# XBee1.net
KiCad netlist of a schematic drawn in EAGLE
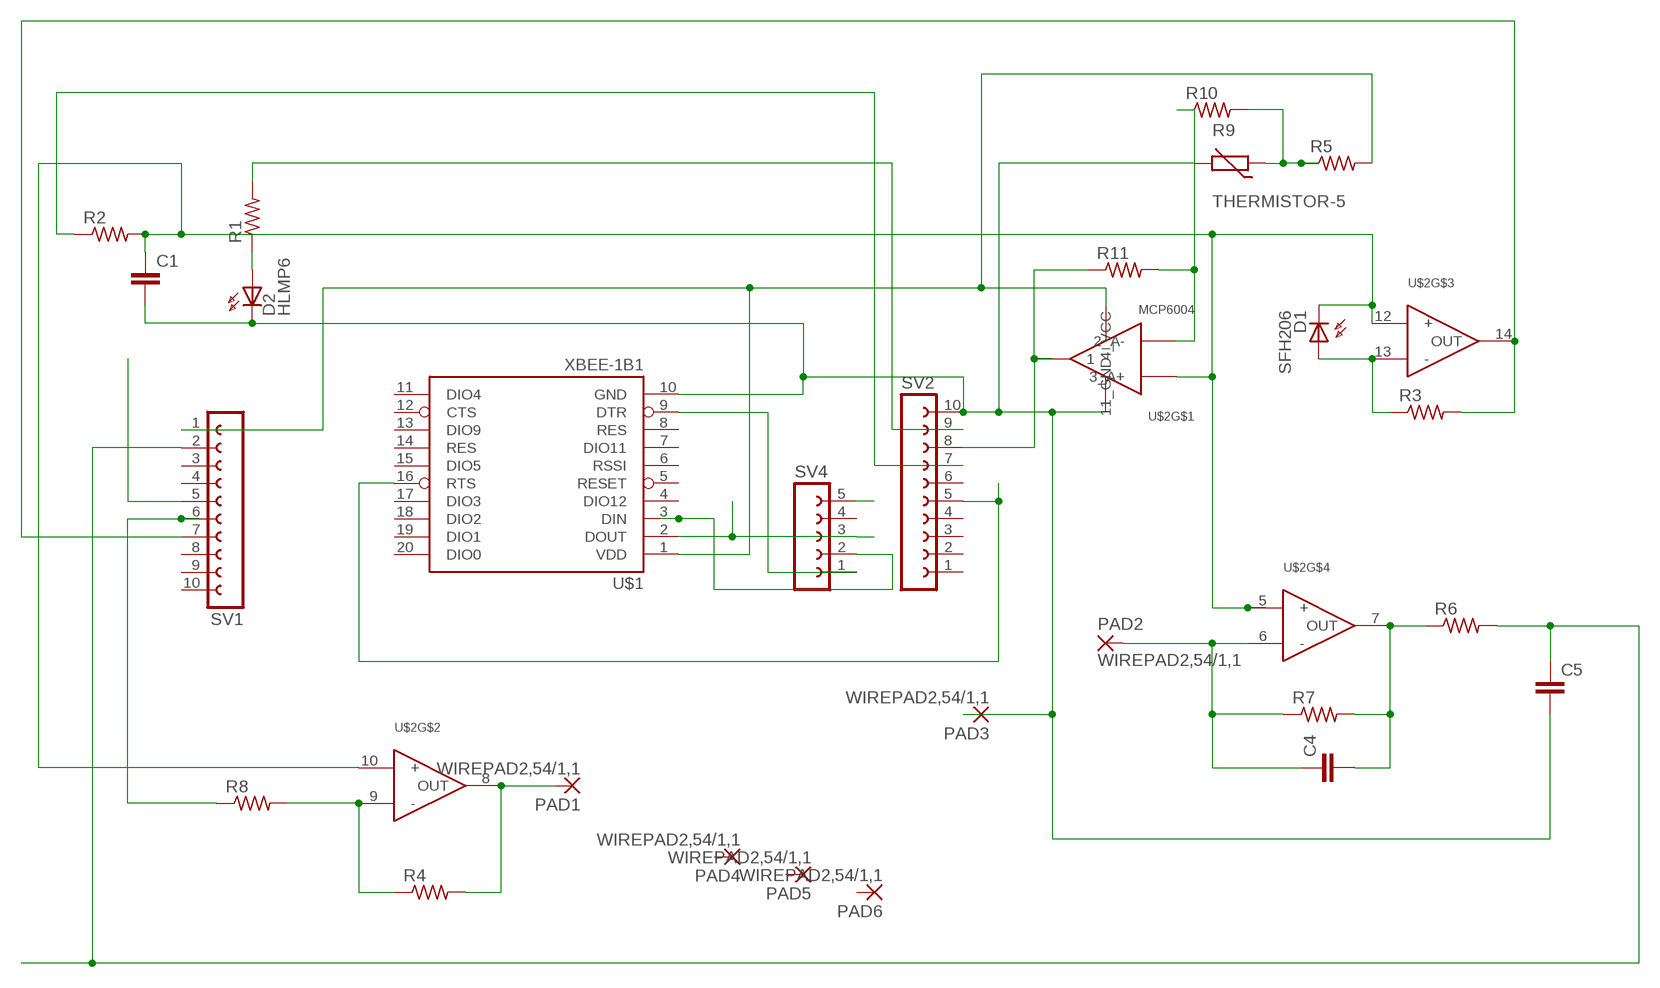
[diagram p0: schematic, sheet 1]

(export (version "E")
  (design (tool "Eeschema 10.0.6"))
  (components
    (comp (ref "C1")
      (value "C-EUC1206")
      (footprint "eagle-import:C1206")
      (libsource (lib "eagle-import") (part "C-EUC1206"))
    )
    (comp (ref "C4")
      (value "C-EUC1206")
      (footprint "eagle-import:C1206")
      (libsource (lib "eagle-import") (part "C-EUC1206"))
    )
    (comp (ref "C5")
      (value "C-EUC1206")
      (footprint "eagle-import:C1206")
      (libsource (lib "eagle-import") (part "C-EUC1206"))
    )
    (comp (ref "D1")
      (value "SFH206")
      (footprint "eagle-import:SFH206")
      (fields (field (name "MPN") "SFH206K"))
      (libsource (lib "eagle-import") (part "SFH206"))
    )
    (comp (ref "D2")
      (value "HLMP6")
      (footprint "eagle-import:HLMP6")
      (fields (field (name "MF") "AGILENT TECHNOLOGIES") (field (name "MPN") "HLMP-6500"))
      (libsource (lib "eagle-import") (part "HLMP6"))
    )
    (comp (ref "PAD1")
      (value "WIREPAD2,54/1,1")
      (footprint "eagle-import:2,54_1,1")
      (libsource (lib "eagle-import") (part "WIREPAD2,54/1,1"))
    )
    (comp (ref "PAD2")
      (value "WIREPAD2,54/1,1")
      (footprint "eagle-import:2,54_1,1")
      (libsource (lib "eagle-import") (part "WIREPAD2,54/1,1"))
    )
    (comp (ref "PAD3")
      (value "WIREPAD2,54/1,1")
      (footprint "eagle-import:2,54_1,1")
      (libsource (lib "eagle-import") (part "WIREPAD2,54/1,1"))
    )
    (comp (ref "PAD4")
      (value "WIREPAD2,54/1,1")
      (footprint "eagle-import:2,54_1,1")
      (libsource (lib "eagle-import") (part "WIREPAD2,54/1,1"))
    )
    (comp (ref "PAD5")
      (value "WIREPAD2,54/1,1")
      (footprint "eagle-import:2,54_1,1")
      (libsource (lib "eagle-import") (part "WIREPAD2,54/1,1"))
    )
    (comp (ref "PAD6")
      (value "WIREPAD2,54/1,1")
      (footprint "eagle-import:2,54_1,1")
      (libsource (lib "eagle-import") (part "WIREPAD2,54/1,1"))
    )
    (comp (ref "R1")
      (value "R-US_M1206")
      (footprint "eagle-import:M1206")
      (libsource (lib "eagle-import") (part "R-US_M1206"))
    )
    (comp (ref "R2")
      (value "R-US_M1206")
      (footprint "eagle-import:M1206")
      (libsource (lib "eagle-import") (part "R-US_M1206"))
    )
    (comp (ref "R3")
      (value "R-US_M1206")
      (footprint "eagle-import:M1206")
      (libsource (lib "eagle-import") (part "R-US_M1206"))
    )
    (comp (ref "R4")
      (value "R-US_M1206")
      (footprint "eagle-import:M1206")
      (libsource (lib "eagle-import") (part "R-US_M1206"))
    )
    (comp (ref "R5")
      (value "R-US_M1206")
      (footprint "eagle-import:M1206")
      (libsource (lib "eagle-import") (part "R-US_M1206"))
    )
    (comp (ref "R6")
      (value "R-US_M1206")
      (footprint "eagle-import:M1206")
      (libsource (lib "eagle-import") (part "R-US_M1206"))
    )
    (comp (ref "R7")
      (value "R-US_M1206")
      (footprint "eagle-import:M1206")
      (libsource (lib "eagle-import") (part "R-US_M1206"))
    )
    (comp (ref "R8")
      (value "R-US_M1206")
      (footprint "eagle-import:M1206")
      (libsource (lib "eagle-import") (part "R-US_M1206"))
    )
    (comp (ref "R9")
      (value "THERMISTOR-5")
      (footprint "eagle-import:R-5")
      (libsource (lib "eagle-import") (part "THERMISTOR-5"))
    )
    (comp (ref "R10")
      (value "R-US_M1206")
      (footprint "eagle-import:M1206")
      (libsource (lib "eagle-import") (part "R-US_M1206"))
    )
    (comp (ref "R11")
      (value "R-US_M1206")
      (footprint "eagle-import:M1206")
      (libsource (lib "eagle-import") (part "R-US_M1206"))
    )
    (comp (ref "SV1")
      (value "FE10-1")
      (footprint "eagle-import:FE10")
      (libsource (lib "eagle-import") (part "FE10-1"))
    )
    (comp (ref "SV2")
      (value "FE10-1")
      (footprint "eagle-import:FE10")
      (libsource (lib "eagle-import") (part "FE10-1"))
    )
    (comp (ref "SV4")
      (value "FE05-1")
      (footprint "eagle-import:FE05-1")
      (libsource (lib "eagle-import") (part "FE05-1"))
    )
    (comp (ref "U$1")
      (value "XBEE-1B1")
      (footprint "eagle-import:XBEE-1")
      (libsource (lib "eagle-import") (part "XBEE-1B1"))
    )
    (comp (ref "U$2")
      (value "MCP6004")
      (footprint "eagle-import:SO014")
      (libsource (lib "eagle-import") (part "MCP6004"))
    )
  )
  (nets
    (net (code "1") (name "Net-(C5-Pad1)") (class "Default")
      (node (ref "C5") (pin "1") (pinfunction "1_1") (pintype "passive"))
      (node (ref "R6") (pin "2") (pinfunction "2_2") (pintype "passive"))
      (node (ref "SV1") (pin "2") (pinfunction "2_2") (pintype "passive"))
    )
    (net (code "2") (name "Net-(D1-C)") (class "Default")
      (node (ref "C1") (pin "1") (pinfunction "1_1") (pintype "passive"))
      (node (ref "D1") (pin "K") (pinfunction "C_K") (pintype "passive"))
      (node (ref "R2") (pin "2") (pinfunction "2_2") (pintype "passive"))
      (node (ref "U$2") (pin "10") (pinfunction "+_10") (pintype "bidirectional"))
      (node (ref "U$2") (pin "12") (pinfunction "+_12") (pintype "bidirectional"))
      (node (ref "U$2") (pin "3") (pinfunction "3_A+_3") (pintype "bidirectional"))
      (node (ref "U$2") (pin "5") (pinfunction "+_5") (pintype "bidirectional"))
    )
    (net (code "3") (name "Net-(D2-PadA)") (class "Default")
      (node (ref "D2") (pin "A") (pinfunction "A_A") (pintype "passive"))
      (node (ref "R1") (pin "1") (pinfunction "1_1") (pintype "passive"))
    )
    (net (code "4") (name "Net-(PAD1-P)") (class "Default")
      (node (ref "PAD1") (pin "1") (pinfunction "P_1") (pintype "passive"))
      (node (ref "R4") (pin "2") (pinfunction "2_2") (pintype "passive"))
      (node (ref "U$2") (pin "8") (pinfunction "OUT_8") (pintype "bidirectional"))
    )
    (net (code "5") (name "Net-(PAD2-P)") (class "Default")
      (node (ref "C4") (pin "1") (pinfunction "1_1") (pintype "passive"))
      (node (ref "PAD2") (pin "1") (pinfunction "P_1") (pintype "passive"))
      (node (ref "R7") (pin "1") (pinfunction "1_1") (pintype "passive"))
      (node (ref "U$2") (pin "6") (pinfunction "-_6") (pintype "bidirectional"))
    )
    (net (code "6") (name "Net-(PAD3-P)") (class "Default")
      (node (ref "C1") (pin "2") (pinfunction "2_2") (pintype "passive"))
      (node (ref "C5") (pin "2") (pinfunction "2_2") (pintype "passive"))
      (node (ref "D2") (pin "K") (pinfunction "K_K") (pintype "passive"))
      (node (ref "PAD3") (pin "1") (pinfunction "P_1") (pintype "passive"))
      (node (ref "R9") (pin "2") (pinfunction "2_2") (pintype "passive"))
      (node (ref "SV2") (pin "10") (pinfunction "10_10") (pintype "passive"))
      (node (ref "U$1") (pin "10") (pinfunction "GND_10") (pintype "power_in"))
      (node (ref "U$2") (pin "4") (pinfunction "4_VCC_4") (pintype "power_in"))
    )
    (net (code "7") (name "Net-(R1-Pad2)") (class "Default")
      (node (ref "R1") (pin "2") (pinfunction "2_2") (pintype "passive"))
      (node (ref "SV2") (pin "9") (pinfunction "9_9") (pintype "passive"))
    )
    (net (code "8") (name "Net-(R2-Pad1)") (class "Default")
      (node (ref "R2") (pin "1") (pinfunction "1_1") (pintype "passive"))
      (node (ref "SV2") (pin "7") (pinfunction "7_7") (pintype "passive"))
    )
    (net (code "9") (name "Net-(R8-Pad1)") (class "Default")
      (node (ref "R8") (pin "1") (pinfunction "1_1") (pintype "passive"))
      (node (ref "SV1") (pin "6") (pinfunction "6_6") (pintype "passive"))
    )
    (net (code "10") (name "Net-(R10-Pad2)") (class "Default")
      (node (ref "R10") (pin "2") (pinfunction "2_2") (pintype "passive"))
      (node (ref "R5") (pin "1") (pinfunction "1_1") (pintype "passive"))
      (node (ref "R9") (pin "1") (pinfunction "1_1") (pintype "passive"))
    )
    (net (code "11") (name "Net-(R11-Pad1)") (class "Default")
      (node (ref "R11") (pin "1") (pinfunction "1_1") (pintype "passive"))
      (node (ref "SV2") (pin "8") (pinfunction "8_8") (pintype "passive"))
      (node (ref "U$2") (pin "1") (pinfunction "1_1") (pintype "bidirectional"))
    )
    (net (code "12") (name "Net-(U$1-DIN)") (class "Default")
      (node (ref "SV4") (pin "2") (pinfunction "2_2") (pintype "passive"))
      (node (ref "U$1") (pin "3") (pinfunction "DIN_3") (pintype "input"))
    )
    (net (code "13") (name "Net-(U$1-DOUT)") (class "Default")
      (node (ref "SV4") (pin "3") (pinfunction "3_3") (pintype "passive"))
      (node (ref "U$1") (pin "2") (pinfunction "DOUT_2") (pintype "output"))
    )
    (net (code "14") (name "Net-(U$1-DTR)") (class "Default")
      (node (ref "SV4") (pin "1") (pinfunction "1_1") (pintype "passive"))
      (node (ref "U$1") (pin "9") (pinfunction "DTR_9") (pintype "bidirectional"))
    )
    (net (code "15") (name "Net-(U$1-RTS)") (class "Default")
      (node (ref "SV2") (pin "5") (pinfunction "5_5") (pintype "passive"))
      (node (ref "U$1") (pin "16") (pinfunction "RTS_16") (pintype "input"))
    )
    (net (code "16") (name "Net-(U$1-VDD)") (class "Default")
      (node (ref "R5") (pin "2") (pinfunction "2_2") (pintype "passive"))
      (node (ref "SV1") (pin "1") (pinfunction "1_1") (pintype "passive"))
      (node (ref "U$1") (pin "1") (pinfunction "VDD_1") (pintype "power_in"))
      (node (ref "U$2") (pin "11") (pinfunction "11_GND_11") (pintype "power_in"))
    )
    (net (code "17") (name "Net-(U$2A-2_A-)") (class "Default")
      (node (ref "R10") (pin "1") (pinfunction "1_1") (pintype "passive"))
      (node (ref "R11") (pin "2") (pinfunction "2_2") (pintype "passive"))
      (node (ref "U$2") (pin "2") (pinfunction "2_A-_2") (pintype "bidirectional"))
    )
    (net (code "18") (name "Net-(U$2B--)") (class "Default")
      (node (ref "R4") (pin "1") (pinfunction "1_1") (pintype "passive"))
      (node (ref "R8") (pin "2") (pinfunction "2_2") (pintype "passive"))
      (node (ref "U$2") (pin "9") (pinfunction "-_9") (pintype "bidirectional"))
    )
    (net (code "19") (name "Net-(U$2C--)") (class "Default")
      (node (ref "D1") (pin "A") (pinfunction "A_A") (pintype "passive"))
      (node (ref "R3") (pin "1") (pinfunction "1_1") (pintype "passive"))
      (node (ref "U$2") (pin "13") (pinfunction "-_13") (pintype "bidirectional"))
    )
    (net (code "20") (name "Net-(U$2C-OUT)") (class "Default")
      (node (ref "R3") (pin "2") (pinfunction "2_2") (pintype "passive"))
      (node (ref "SV1") (pin "7") (pinfunction "7_7") (pintype "passive"))
      (node (ref "U$2") (pin "14") (pinfunction "OUT_14") (pintype "bidirectional"))
    )
    (net (code "21") (name "Net-(U$2D-OUT)") (class "Default")
      (node (ref "C4") (pin "2") (pinfunction "2_2") (pintype "passive"))
      (node (ref "R6") (pin "1") (pinfunction "1_1") (pintype "passive"))
      (node (ref "R7") (pin "2") (pinfunction "2_2") (pintype "passive"))
      (node (ref "U$2") (pin "7") (pinfunction "OUT_7") (pintype "bidirectional"))
    )
    (net (code "22") (name "unconnected-(PAD4-P-Pad1)") (class "Default")
      (node (ref "PAD4") (pin "1") (pinfunction "P_1") (pintype "passive"))
    )
    (net (code "23") (name "unconnected-(PAD5-P-Pad1)") (class "Default")
      (node (ref "PAD5") (pin "1") (pinfunction "P_1") (pintype "passive"))
    )
    (net (code "24") (name "unconnected-(PAD6-P-Pad1)") (class "Default")
      (node (ref "PAD6") (pin "1") (pinfunction "P_1") (pintype "passive"))
    )
    (net (code "25") (name "unconnected-(SV1-Pad3)") (class "Default")
      (node (ref "SV1") (pin "3") (pinfunction "3_3") (pintype "passive"))
    )
    (net (code "26") (name "unconnected-(SV1-Pad4)") (class "Default")
      (node (ref "SV1") (pin "4") (pinfunction "4_4") (pintype "passive"))
    )
    (net (code "27") (name "unconnected-(SV1-Pad5)") (class "Default")
      (node (ref "SV1") (pin "5") (pinfunction "5_5") (pintype "passive"))
    )
    (net (code "28") (name "unconnected-(SV1-Pad8)") (class "Default")
      (node (ref "SV1") (pin "8") (pinfunction "8_8") (pintype "passive"))
    )
    (net (code "29") (name "unconnected-(SV1-Pad9)") (class "Default")
      (node (ref "SV1") (pin "9") (pinfunction "9_9") (pintype "passive"))
    )
    (net (code "30") (name "unconnected-(SV1-Pad10)") (class "Default")
      (node (ref "SV1") (pin "10") (pinfunction "10_10") (pintype "passive"))
    )
    (net (code "31") (name "unconnected-(SV2-Pad1)") (class "Default")
      (node (ref "SV2") (pin "1") (pinfunction "1_1") (pintype "passive"))
    )
    (net (code "32") (name "unconnected-(SV2-Pad2)") (class "Default")
      (node (ref "SV2") (pin "2") (pinfunction "2_2") (pintype "passive"))
    )
    (net (code "33") (name "unconnected-(SV2-Pad3)") (class "Default")
      (node (ref "SV2") (pin "3") (pinfunction "3_3") (pintype "passive"))
    )
    (net (code "34") (name "unconnected-(SV2-Pad4)") (class "Default")
      (node (ref "SV2") (pin "4") (pinfunction "4_4") (pintype "passive"))
    )
    (net (code "35") (name "unconnected-(SV2-Pad6)") (class "Default")
      (node (ref "SV2") (pin "6") (pinfunction "6_6") (pintype "passive"))
    )
    (net (code "36") (name "unconnected-(SV4-Pad4)") (class "Default")
      (node (ref "SV4") (pin "4") (pinfunction "4_4") (pintype "passive"))
    )
    (net (code "37") (name "unconnected-(SV4-Pad5)") (class "Default")
      (node (ref "SV4") (pin "5") (pinfunction "5_5") (pintype "passive"))
    )
    (net (code "38") (name "unconnected-(U$1-CTS-Pad12)") (class "Default")
      (node (ref "U$1") (pin "12") (pinfunction "CTS_12") (pintype "output"))
    )
    (net (code "39") (name "unconnected-(U$1-DIO0-Pad20)") (class "Default")
      (node (ref "U$1") (pin "20") (pinfunction "DIO0_20") (pintype "bidirectional"))
    )
    (net (code "40") (name "unconnected-(U$1-DIO1-Pad19)") (class "Default")
      (node (ref "U$1") (pin "19") (pinfunction "DIO1_19") (pintype "bidirectional"))
    )
    (net (code "41") (name "unconnected-(U$1-DIO2-Pad18)") (class "Default")
      (node (ref "U$1") (pin "18") (pinfunction "DIO2_18") (pintype "bidirectional"))
    )
    (net (code "42") (name "unconnected-(U$1-DIO3-Pad17)") (class "Default")
      (node (ref "U$1") (pin "17") (pinfunction "DIO3_17") (pintype "bidirectional"))
    )
    (net (code "43") (name "unconnected-(U$1-DIO4-Pad11)") (class "Default")
      (node (ref "U$1") (pin "11") (pinfunction "DIO4_11") (pintype "bidirectional"))
    )
    (net (code "44") (name "unconnected-(U$1-DIO5-Pad15)") (class "Default")
      (node (ref "U$1") (pin "15") (pinfunction "DIO5_15") (pintype "bidirectional"))
    )
    (net (code "45") (name "unconnected-(U$1-DIO9-Pad13)") (class "Default")
      (node (ref "U$1") (pin "13") (pinfunction "DIO9_13") (pintype "bidirectional"))
    )
    (net (code "46") (name "unconnected-(U$1-DIO11-Pad7)") (class "Default")
      (node (ref "U$1") (pin "7") (pinfunction "DIO11_7") (pintype "bidirectional"))
    )
    (net (code "47") (name "unconnected-(U$1-DIO12-Pad4)") (class "Default")
      (node (ref "U$1") (pin "4") (pinfunction "DIO12_4") (pintype "bidirectional"))
    )
    (net (code "48") (name "unconnected-(U$1-RES-Pad8)") (class "Default")
      (node (ref "U$1") (pin "8") (pinfunction "RES_8") (pintype "bidirectional"))
    )
    (net (code "49") (name "unconnected-(U$1-RES-Pad14)") (class "Default")
      (node (ref "U$1") (pin "14") (pinfunction "RES_14") (pintype "bidirectional"))
    )
    (net (code "50") (name "unconnected-(U$1-RESET-Pad5)") (class "Default")
      (node (ref "U$1") (pin "5") (pinfunction "RESET_5") (pintype "input"))
    )
    (net (code "51") (name "unconnected-(U$1-RSSI-Pad6)") (class "Default")
      (node (ref "U$1") (pin "6") (pinfunction "RSSI_6") (pintype "bidirectional"))
    )
  )
)
